# Power.net
KiCad netlist of a schematic drawn in Altium Designer
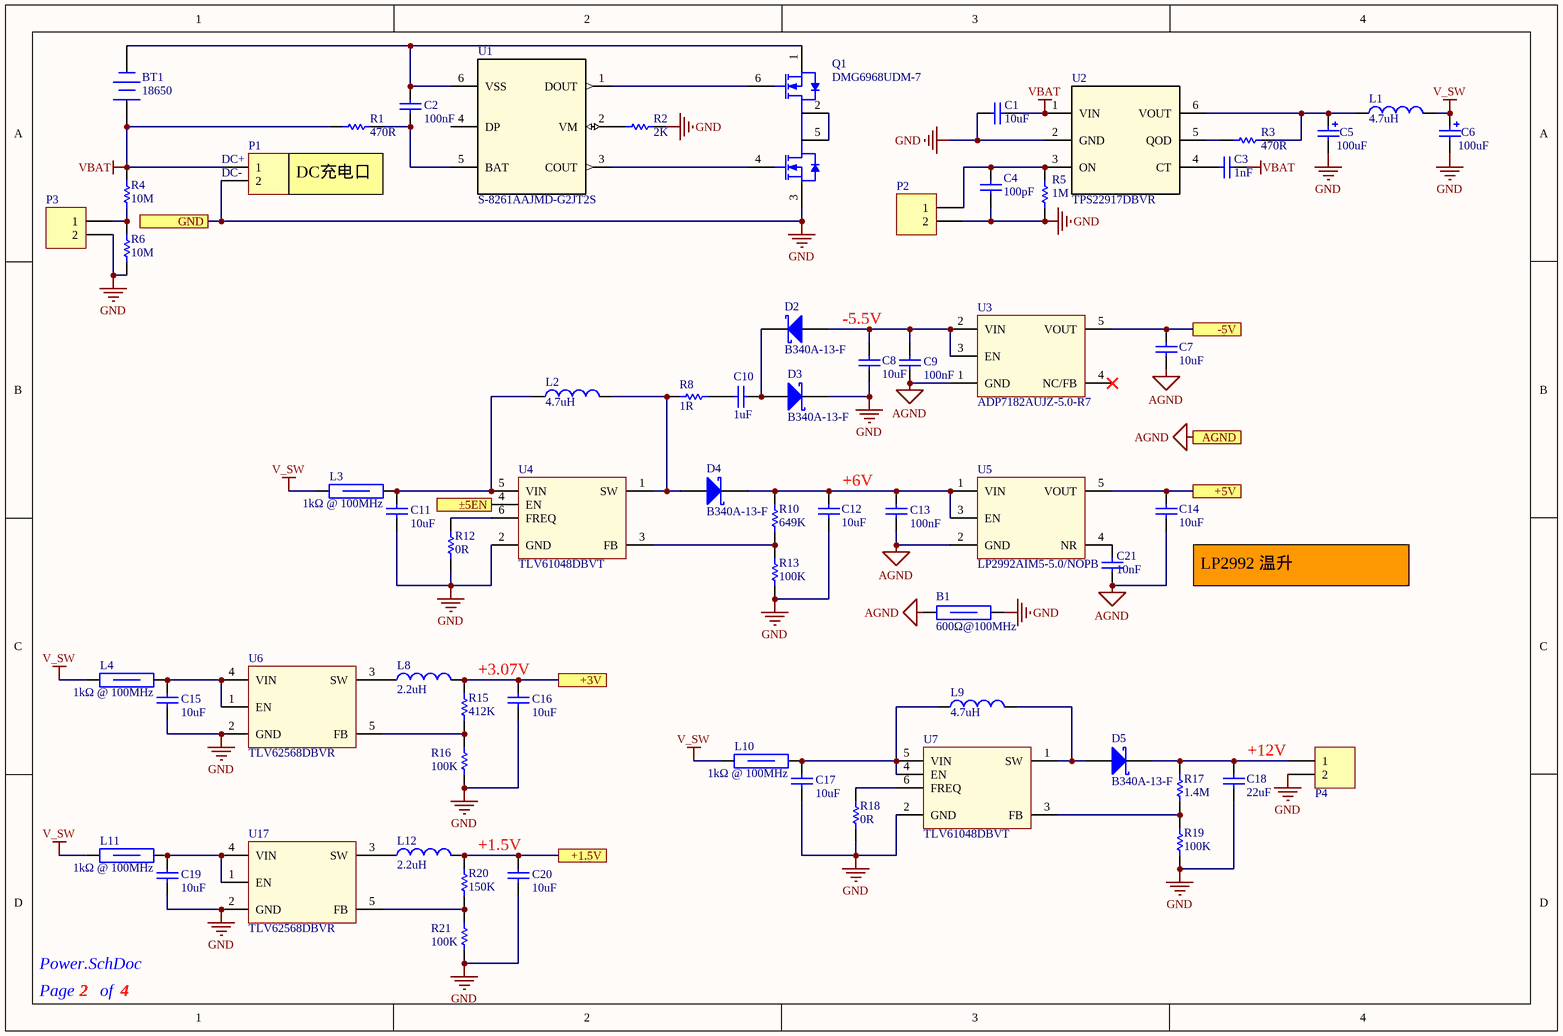
[diagram p0: Power.SchDoc]

(export (version "E")
  (design (tool "Eeschema 10.0.6"))
  (components
    (comp (ref "B1")
      (value "600Ω@100MHz")
      (footprint "R0805_L")
      (description "600Ω @ 100MHz \r\n线路数 1 \r\n额定电流（最大） 600mA \r\n直流电阻（DCR）（最大） 210mΩ")
      (libsource (lib "00Lib") (part "600Ω@100MHz"))
    )
    (comp (ref "BT1")
      (value "18650")
      (footprint "CP1X2")
      (description "18650单节直插电池仓")
      (libsource (lib "00Lib") (part "Battery_18650_DIP"))
    )
    (comp (ref "C1")
      (value "10uF")
      (footprint "R0805_C")
      (description "精度 ±10% \r\n容值 10uF \r\n额定电压 16V \r\n温漂系数（介质材料) X7R")
      (libsource (lib "00Lib") (part "10uF/0805/16V"))
    )
    (comp (ref "C2")
      (value "100nF")
      (footprint "R0603_C")
      (description "精度 ±10% \r\n容值 100nF \r\n额定电压 50V \r\n温漂系数（介质材料) X7R")
      (libsource (lib "00Lib") (part "100nF/0603/50V"))
    )
    (comp (ref "C3")
      (value "1nF")
      (footprint "R0603_C")
      (description "精度 ±5% \r\n容值 1nF \r\n额定电压 50V \r\n温漂系数（介质材料) C0G")
      (libsource (lib "00Lib") (part "1nF/0603/50V"))
    )
    (comp (ref "C4")
      (value "100pF")
      (footprint "R0603_C")
      (description "精度 ±5% \r\n容值 100pF \r\n额定电压 50V \r\n温漂系数（介质材料) C0G")
      (libsource (lib "00Lib") (part "100pF/0603/50V"))
    )
    (comp (ref "C5")
      (value "100uF")
      (footprint "CASE-E_7343")
      (description "钽电容 \r\n精度 ±10% \r\n容值 100uF \r\n额定电压 16V \r\nESR串联电阻 900 mΩ @ 100kHz \r\n工作温度 -55℃~125℃")
      (libsource (lib "00Lib") (part "Cap Pol/100uF/16V"))
    )
    (comp (ref "C6")
      (value "100uF")
      (footprint "CASE-E_7343")
      (description "钽电容 \r\n精度 ±10% \r\n容值 100uF \r\n额定电压 16V \r\nESR串联电阻 900 mΩ @ 100kHz \r\n工作温度 -55℃~125℃")
      (libsource (lib "00Lib") (part "Cap Pol/100uF/16V"))
    )
    (comp (ref "C7")
      (value "10uF")
      (footprint "R0805_C")
      (description "精度 ±10% \r\n容值 10uF \r\n额定电压 16V \r\n温漂系数（介质材料) X7R")
      (libsource (lib "00Lib") (part "10uF/0805/16V"))
    )
    (comp (ref "C8")
      (value "10uF")
      (footprint "R0805_C")
      (description "精度 ±10% \r\n容值 10uF \r\n额定电压 16V \r\n温漂系数（介质材料) X7R")
      (libsource (lib "00Lib") (part "10uF/0805/16V"))
    )
    (comp (ref "C9")
      (value "100nF")
      (footprint "R0603_C")
      (description "精度 ±10% \r\n容值 100nF \r\n额定电压 50V \r\n温漂系数（介质材料) X7R")
      (libsource (lib "00Lib") (part "100nF/0603/50V"))
    )
    (comp (ref "C10")
      (value "1uF")
      (footprint "R0603_C")
      (description "精度 ±10% \r\n容值 1uF \r\n额定电压 50V \r\n温漂系数（介质材料) X7R")
      (libsource (lib "00Lib") (part "1uF/0603/50V"))
    )
    (comp (ref "C11")
      (value "10uF")
      (footprint "R0805_C")
      (description "精度 ±10% \r\n容值 10uF \r\n额定电压 16V \r\n温漂系数（介质材料) X7R")
      (libsource (lib "00Lib") (part "10uF/0805/16V"))
    )
    (comp (ref "C12")
      (value "10uF")
      (footprint "R0805_C")
      (description "精度 ±10% \r\n容值 10uF \r\n额定电压 16V \r\n温漂系数（介质材料) X7R")
      (libsource (lib "00Lib") (part "10uF/0805/16V"))
    )
    (comp (ref "C13")
      (value "100nF")
      (footprint "R0603_C")
      (description "精度 ±10% \r\n容值 100nF \r\n额定电压 50V \r\n温漂系数（介质材料) X7R")
      (libsource (lib "00Lib") (part "100nF/0603/50V"))
    )
    (comp (ref "C14")
      (value "10uF")
      (footprint "R0805_C")
      (description "精度 ±10% \r\n容值 10uF \r\n额定电压 16V \r\n温漂系数（介质材料) X7R")
      (libsource (lib "00Lib") (part "10uF/0805/16V"))
    )
    (comp (ref "C15")
      (value "10uF")
      (footprint "R0805_C")
      (description "精度 ±10% \r\n容值 10uF \r\n额定电压 16V \r\n温漂系数（介质材料) X7R")
      (libsource (lib "00Lib") (part "10uF/0805/16V"))
    )
    (comp (ref "C16")
      (value "10uF")
      (footprint "R0805_C")
      (description "精度 ±10% \r\n容值 10uF \r\n额定电压 16V \r\n温漂系数（介质材料) X7R")
      (libsource (lib "00Lib") (part "10uF/0805/16V"))
    )
    (comp (ref "C17")
      (value "10uF")
      (footprint "R0805_C")
      (description "精度 ±10% \r\n容值 10uF \r\n额定电压 16V \r\n温漂系数（介质材料) X7R")
      (libsource (lib "00Lib") (part "10uF/0805/16V"))
    )
    (comp (ref "C18")
      (value "22uF")
      (footprint "R1210_C")
      (description "±10% \r\n容值 22uF \r\n额定电压 25V \r\n温漂系数（介质材料) X7R")
      (libsource (lib "00Lib") (part "22uF/1210/25V"))
    )
    (comp (ref "C19")
      (value "10uF")
      (footprint "R0805_C")
      (description "精度 ±10% \r\n容值 10uF \r\n额定电压 16V \r\n温漂系数（介质材料) X7R")
      (libsource (lib "00Lib") (part "10uF/0805/16V"))
    )
    (comp (ref "C20")
      (value "10uF")
      (footprint "R0805_C")
      (description "精度 ±10% \r\n容值 10uF \r\n额定电压 16V \r\n温漂系数（介质材料) X7R")
      (libsource (lib "00Lib") (part "10uF/0805/16V"))
    )
    (comp (ref "C21")
      (value "10nF")
      (footprint "R0603_C")
      (description "精度 ±5% \r\n容值 10nF \r\n额定电压 50V \r\n温漂系数（介质材料) C0G")
      (libsource (lib "00Lib") (part "10nF/0603/C0G/50V"))
    )
    (comp (ref "D2")
      (value "B340A-13-F")
      (footprint "SMA(DO-214AC)_S2")
      (description "直流反向耐压（Vr） 40V \r\n平均整流电流（Io） 3A \r\n正向压降（Vf） 550mV @ 3A")
      (libsource (lib "00Lib") (part "B340A-13-F"))
    )
    (comp (ref "D3")
      (value "B340A-13-F")
      (footprint "SMA(DO-214AC)_S2")
      (description "直流反向耐压（Vr） 40V \r\n平均整流电流（Io） 3A \r\n正向压降（Vf） 550mV @ 3A")
      (libsource (lib "00Lib") (part "B340A-13-F"))
    )
    (comp (ref "D4")
      (value "B340A-13-F")
      (footprint "SMA(DO-214AC)_S2")
      (description "直流反向耐压（Vr） 40V \r\n平均整流电流（Io） 3A \r\n正向压降（Vf） 550mV @ 3A")
      (libsource (lib "00Lib") (part "B340A-13-F"))
    )
    (comp (ref "D5")
      (value "B340A-13-F")
      (footprint "SMA(DO-214AC)_S2")
      (description "直流反向耐压（Vr） 40V \r\n平均整流电流（Io） 3A \r\n正向压降（Vf） 550mV @ 3A")
      (libsource (lib "00Lib") (part "B340A-13-F"))
    )
    (comp (ref "L1")
      (value "4.7uH")
      (footprint "NR2520")
      (description "精度 ±20% \r\n饱和电流 1.37A \r\n温升电流0.92A\r\n直流电阻（内阻） 377mΩ \r\n电感值 4.7uH")
      (libsource (lib "00Lib") (part "4.7uH/NR2520"))
    )
    (comp (ref "L2")
      (value "4.7uH")
      (footprint "NR2520")
      (description "精度 ±20% \r\n饱和电流 1.37A \r\n温升电流0.92A\r\n直流电阻（内阻） 377mΩ \r\n电感值 4.7uH")
      (libsource (lib "00Lib") (part "4.7uH/NR2520"))
    )
    (comp (ref "L3")
      (value "1kΩ @ 100MHz")
      (footprint "R1206_L")
      (description "阻抗 @ 频率 1kΩ @ 100MHz \r\n线路数 1 \r\n额定电流（最大） 2A \r\n直流电阻（DCR）（最大） 120mΩ")
      (libsource (lib "00Lib") (part "1kΩ@100MHz"))
    )
    (comp (ref "L4")
      (value "1kΩ @ 100MHz")
      (footprint "R1206_L")
      (description "阻抗 @ 频率 1kΩ @ 100MHz \r\n线路数 1 \r\n额定电流（最大） 2A \r\n直流电阻（DCR）（最大） 120mΩ")
      (libsource (lib "00Lib") (part "1kΩ@100MHz"))
    )
    (comp (ref "L8")
      (value "2.2uH")
      (footprint "NR2016")
      (description "精度 ±20% \r\n饱和电流 1.3A \r\n温升电流1.15A\r\n直流电阻（内阻） 175mΩ \r\n电感值 2.2uH")
      (libsource (lib "00Lib") (part "2.2uH/NR2016"))
    )
    (comp (ref "L9")
      (value "4.7uH")
      (footprint "NR2520")
      (description "精度 ±20% \r\n饱和电流 1.37A \r\n温升电流0.92A\r\n直流电阻（内阻） 377mΩ \r\n电感值 4.7uH")
      (libsource (lib "00Lib") (part "4.7uH/NR2520"))
    )
    (comp (ref "L10")
      (value "1kΩ @ 100MHz")
      (footprint "R1206_L")
      (description "阻抗 @ 频率 1kΩ @ 100MHz \r\n线路数 1 \r\n额定电流（最大） 2A \r\n直流电阻（DCR）（最大） 120mΩ")
      (libsource (lib "00Lib") (part "1kΩ@100MHz"))
    )
    (comp (ref "L11")
      (value "1kΩ @ 100MHz")
      (footprint "R1206_L")
      (description "阻抗 @ 频率 1kΩ @ 100MHz \r\n线路数 1 \r\n额定电流（最大） 2A \r\n直流电阻（DCR）（最大） 120mΩ")
      (libsource (lib "00Lib") (part "1kΩ@100MHz"))
    )
    (comp (ref "L12")
      (value "2.2uH")
      (footprint "NR2016")
      (description "精度 ±20% \r\n饱和电流 1.3A \r\n温升电流1.15A\r\n直流电阻（内阻） 175mΩ \r\n电感值 2.2uH")
      (libsource (lib "00Lib") (part "2.2uH/NR2016"))
    )
    (comp (ref "P1")
      (value "Header 2")
      (footprint "CP1X2")
      (description "Header, 2-Pin")
      (libsource (lib "") (part "Header 2_1"))
    )
    (comp (ref "P2")
      (value "Header 2")
      (footprint "CP1X2")
      (description "Header, 2-Pin")
      (libsource (lib "00Lib") (part "Header 2"))
    )
    (comp (ref "P3")
      (value "Header 2")
      (footprint "CP1X2")
      (description "Header, 2-Pin")
      (libsource (lib "00Lib") (part "Header 2"))
    )
    (comp (ref "P4")
      (value "Header 2")
      (footprint "CP1X2")
      (description "Header, 2-Pin")
      (libsource (lib "") (part "Header 2_1"))
    )
    (comp (ref "Q1")
      (value "DMG6968UDM-7")
      (footprint "DBV0006A_N")
      (libsource (lib "00Lib") (part "DMG6968UDM-7"))
    )
    (comp (ref "R1")
      (value "470R")
      (footprint "R0603_R")
      (description "精度 ±1% \r\n温度系数 ±100ppm/℃ \r\n功率 0.1W")
      (libsource (lib "00Lib") (part "470R/0603"))
    )
    (comp (ref "R2")
      (value "2K")
      (footprint "R0603_R")
      (description "精度 ±1% \r\n阻值 2kΩ \r\n温度系数 ±100ppm/℃ \r\n功率 0.1W")
      (libsource (lib "00Lib") (part "2K/0603"))
    )
    (comp (ref "R3")
      (value "470R")
      (footprint "R0603_R")
      (description "精度 ±1% \r\n温度系数 ±100ppm/℃ \r\n功率 0.1W")
      (libsource (lib "00Lib") (part "470R/0603"))
    )
    (comp (ref "R4")
      (value "10M")
      (footprint "R0603_R")
      (description "温度系数 ±250ppm/℃ \r\n精度 ±1% \r\n阻值 10MΩ \r\n功率 0.1W")
      (libsource (lib "00Lib") (part "10M/0603"))
    )
    (comp (ref "R5")
      (value "1M")
      (footprint "R0603_R")
      (description "阻值 1MΩ \r\n精度 ±1% \r\n温度系数 ±100ppm/℃ \r\n功率 0.1W")
      (libsource (lib "00Lib") (part "1M/0603"))
    )
    (comp (ref "R6")
      (value "10M")
      (footprint "R0603_R")
      (description "温度系数 ±250ppm/℃ \r\n精度 ±1% \r\n阻值 10MΩ \r\n功率 0.1W")
      (libsource (lib "00Lib") (part "10M/0603"))
    )
    (comp (ref "R8")
      (value "1R")
      (footprint "R0603_R")
      (description "±250ppm/℃ \r\n精度 ±1% \r\n阻值 1Ω \r\n功率 0.1W")
      (libsource (lib "00Lib") (part "1R/0603"))
    )
    (comp (ref "R10")
      (value "649K")
      (footprint "R0603_R")
      (description "649kΩ \r\n精度 ±1% \r\n温度系数 ±100ppm/℃ \r\n功率 0.1W")
      (libsource (lib "00Lib") (part "649K/0603"))
    )
    (comp (ref "R12")
      (value "0R")
      (footprint "R0603_R")
      (description "精度 ±1% \r\n阻值 0Ω \r\n功率 0.1W")
      (libsource (lib "00Lib") (part "0R/0603"))
    )
    (comp (ref "R13")
      (value "100K")
      (footprint "R0603_R")
      (description "精度 ±1% \r\n阻值 100kΩ \r\n温度系数 ±100ppm/℃ \r\n功率 0.1W")
      (libsource (lib "00Lib") (part "100K/0603"))
    )
    (comp (ref "R15")
      (value "412K")
      (footprint "R0603_R")
      (description "412kΩ \r\n精度 ±1% \r\n温度系数 ±100ppm/℃ \r\n功率 0.1W")
      (libsource (lib "00Lib") (part "412K/0603"))
    )
    (comp (ref "R16")
      (value "100K")
      (footprint "R0603_R")
      (description "精度 ±1% \r\n阻值 100kΩ \r\n温度系数 ±100ppm/℃ \r\n功率 0.1W")
      (libsource (lib "00Lib") (part "100K/0603"))
    )
    (comp (ref "R17")
      (value "1.4M")
      (footprint "R0603_R")
      (description "±250ppm/℃ \r\n精度 ±1% \r\n阻值 1.4MΩ \r\n功率 0.1W")
      (libsource (lib "00Lib") (part "1.4M/0603"))
    )
    (comp (ref "R18")
      (value "0R")
      (footprint "R0603_R")
      (description "精度 ±1% \r\n阻值 0Ω \r\n功率 0.1W")
      (libsource (lib "00Lib") (part "0R/0603"))
    )
    (comp (ref "R19")
      (value "100K")
      (footprint "R0603_R")
      (description "精度 ±1% \r\n阻值 100kΩ \r\n温度系数 ±100ppm/℃ \r\n功率 0.1W")
      (libsource (lib "00Lib") (part "100K/0603"))
    )
    (comp (ref "R20")
      (value "150K")
      (footprint "R0603_R")
      (description "150kΩ \r\n精度 ±1% \r\n温度系数 ±100ppm/℃ \r\n功率 0.1W")
      (libsource (lib "00Lib") (part "150K/0603"))
    )
    (comp (ref "R21")
      (value "100K")
      (footprint "R0603_R")
      (description "精度 ±1% \r\n阻值 100kΩ \r\n温度系数 ±100ppm/℃ \r\n功率 0.1W")
      (libsource (lib "00Lib") (part "100K/0603"))
    )
    (comp (ref "U1")
      (value "S-8261AAJMD-G2JT2S")
      (footprint "DBV0006A_N")
      (description "单节电池保护芯片\r\n过充4.325V\r\n过放2.5V\r\n过流150mV")
      (libsource (lib "00Lib") (part "S-8261AAJMD-G2JT2S"))
    )
    (comp (ref "U2")
      (value "TPS22917DBVR")
      (footprint "DBV0006A_N")
      (description "2A负载开关")
      (libsource (lib "00Lib") (part "TPS22917DBVR"))
    )
    (comp (ref "U3")
      (value "ADP7182AUJZ-5.0-R7")
      (footprint "SOT23-5")
      (description "–28 V、 −200 mA、低噪声线性稳压器")
      (libsource (lib "00Lib") (part "ADP7182AUJZ-5.0-R7"))
    )
    (comp (ref "U4")
      (value "TLV61048DBVT")
      (footprint "DBV0006A_N")
      (libsource (lib "00Lib") (part "TLV61048DBVT"))
    )
    (comp (ref "U5")
      (value "LP2992AIM5-5.0/NOPB")
      (footprint "SOT23-5")
      (libsource (lib "00Lib") (part "LP2992AIM5-5.0/NOPB"))
    )
    (comp (ref "U6")
      (value "TLV62568DBVR")
      (footprint "SOT23-5")
      (libsource (lib "00Lib") (part "TLV62568DBVR"))
    )
    (comp (ref "U7")
      (value "TLV61048DBVT")
      (footprint "DBV0006A_N")
      (libsource (lib "00Lib") (part "TLV61048DBVT"))
    )
    (comp (ref "U17")
      (value "TLV62568DBVR")
      (footprint "SOT23-5")
      (libsource (lib "00Lib") (part "TLV62568DBVR"))
    )
  )
  (nets
    (net (code "1") (name "/+1.5V") (class "Default")
      (node (ref "C20") (pin "2") (pinfunction "2_2") (pintype "passive"))
      (node (ref "L12") (pin "2") (pinfunction "2_2") (pintype "passive"))
      (node (ref "R20") (pin "2") (pinfunction "2_2") (pintype "passive"))
    )
    (net (code "2") (name "/+3V") (class "Default")
      (node (ref "C16") (pin "2") (pinfunction "2_2") (pintype "passive"))
      (node (ref "L8") (pin "2") (pinfunction "2_2") (pintype "passive"))
      (node (ref "R15") (pin "2") (pinfunction "2_2") (pintype "passive"))
    )
    (net (code "3") (name "/+5V") (class "Default")
      (node (ref "C14") (pin "1") (pinfunction "1_1") (pintype "passive"))
      (node (ref "U5") (pin "5") (pinfunction "VOUT_5") (pintype "power_in"))
    )
    (net (code "4") (name "/-5V") (class "Default")
      (node (ref "C7") (pin "1") (pinfunction "1_1") (pintype "passive"))
      (node (ref "U3") (pin "5") (pinfunction "VOUT_5") (pintype "power_in"))
    )
    (net (code "5") (name "/±5EN") (class "Default")
      (node (ref "U4") (pin "4") (pinfunction "EN_4") (pintype "passive"))
    )
    (net (code "6") (name "AGND") (class "Default")
      (node (ref "B1") (pin "1") (pinfunction "1_1") (pintype "passive"))
      (node (ref "C13") (pin "2") (pinfunction "2_2") (pintype "passive"))
      (node (ref "C14") (pin "2") (pinfunction "2_2") (pintype "passive"))
      (node (ref "C21") (pin "1") (pinfunction "1_1") (pintype "passive"))
      (node (ref "C7") (pin "2") (pinfunction "2_2") (pintype "passive"))
      (node (ref "C9") (pin "2") (pinfunction "2_2") (pintype "passive"))
      (node (ref "U3") (pin "1") (pinfunction "GND_1") (pintype "power_in"))
      (node (ref "U5") (pin "2") (pinfunction "GND_2") (pintype "power_in"))
    )
    (net (code "7") (name "GND") (class "Default")
      (node (ref "B1") (pin "2") (pinfunction "2_2") (pintype "passive"))
      (node (ref "C1") (pin "1") (pinfunction "1_1") (pintype "passive"))
      (node (ref "C11") (pin "1") (pinfunction "1_1") (pintype "passive"))
      (node (ref "C12") (pin "1") (pinfunction "1_1") (pintype "passive"))
      (node (ref "C15") (pin "1") (pinfunction "1_1") (pintype "passive"))
      (node (ref "C16") (pin "1") (pinfunction "1_1") (pintype "passive"))
      (node (ref "C17") (pin "1") (pinfunction "1_1") (pintype "passive"))
      (node (ref "C18") (pin "1") (pinfunction "1_1") (pintype "passive"))
      (node (ref "C19") (pin "1") (pinfunction "1_1") (pintype "passive"))
      (node (ref "C20") (pin "1") (pinfunction "1_1") (pintype "passive"))
      (node (ref "C4") (pin "1") (pinfunction "1_1") (pintype "passive"))
      (node (ref "C5") (pin "2") (pinfunction "2_2") (pintype "passive"))
      (node (ref "C6") (pin "2") (pinfunction "2_2") (pintype "passive"))
      (node (ref "C8") (pin "2") (pinfunction "2_2") (pintype "passive"))
      (node (ref "D3") (pin "2") (pinfunction "K_2") (pintype "passive"))
      (node (ref "P1") (pin "2") (pinfunction "2_2") (pintype "passive"))
      (node (ref "P2") (pin "2") (pinfunction "2_2") (pintype "passive"))
      (node (ref "P3") (pin "2") (pinfunction "2_2") (pintype "passive"))
      (node (ref "P4") (pin "2") (pinfunction "2_2") (pintype "passive"))
      (node (ref "Q1") (pin "3") (pinfunction "S2_3") (pintype "passive"))
      (node (ref "R12") (pin "1") (pinfunction "1_1") (pintype "passive"))
      (node (ref "R13") (pin "1") (pinfunction "1_1") (pintype "passive"))
      (node (ref "R16") (pin "1") (pinfunction "1_1") (pintype "passive"))
      (node (ref "R18") (pin "1") (pinfunction "1_1") (pintype "passive"))
      (node (ref "R19") (pin "1") (pinfunction "1_1") (pintype "passive"))
      (node (ref "R2") (pin "2") (pinfunction "2_2") (pintype "passive"))
      (node (ref "R21") (pin "1") (pinfunction "1_1") (pintype "passive"))
      (node (ref "R5") (pin "1") (pinfunction "1_1") (pintype "passive"))
      (node (ref "R6") (pin "2") (pinfunction "2_2") (pintype "passive"))
      (node (ref "U17") (pin "2") (pinfunction "GND_2") (pintype "power_in"))
      (node (ref "U2") (pin "2") (pinfunction "GND_2") (pintype "passive"))
      (node (ref "U4") (pin "2") (pinfunction "GND_2") (pintype "power_in"))
      (node (ref "U6") (pin "2") (pinfunction "GND_2") (pintype "power_in"))
      (node (ref "U7") (pin "2") (pinfunction "GND_2") (pintype "power_in"))
    )
    (net (code "8") (name "Net-(BT1--)") (class "Default")
      (node (ref "BT1") (pin "2") (pinfunction "-_2") (pintype "passive"))
      (node (ref "C2") (pin "1") (pinfunction "1_1") (pintype "passive"))
      (node (ref "Q1") (pin "1") (pinfunction "S1_1") (pintype "passive"))
      (node (ref "U1") (pin "6") (pinfunction "VSS_6") (pintype "passive"))
    )
    (net (code "9") (name "Net-(C10-Pad2)") (class "Default")
      (node (ref "C10") (pin "2") (pinfunction "2_2") (pintype "passive"))
      (node (ref "R8") (pin "2") (pinfunction "2_2") (pintype "passive"))
    )
    (net (code "10") (name "Net-(D2-A)") (class "Default")
      (node (ref "C8") (pin "1") (pinfunction "1_1") (pintype "passive"))
      (node (ref "C9") (pin "1") (pinfunction "1_1") (pintype "passive"))
      (node (ref "D2") (pin "1") (pinfunction "A_1") (pintype "passive"))
      (node (ref "U3") (pin "2") (pinfunction "VIN_2") (pintype "power_in"))
      (node (ref "U3") (pin "3") (pinfunction "EN_3") (pintype "passive"))
    )
    (net (code "11") (name "Net-(D2-K)") (class "Default")
      (node (ref "C10") (pin "1") (pinfunction "1_1") (pintype "passive"))
      (node (ref "D2") (pin "2") (pinfunction "K_2") (pintype "passive"))
      (node (ref "D3") (pin "1") (pinfunction "A_1") (pintype "passive"))
    )
    (net (code "12") (name "Net-(D4-A)") (class "Default")
      (node (ref "D4") (pin "1") (pinfunction "A_1") (pintype "passive"))
      (node (ref "L2") (pin "2") (pinfunction "2_2") (pintype "passive"))
      (node (ref "R8") (pin "1") (pinfunction "1_1") (pintype "passive"))
      (node (ref "U4") (pin "1") (pinfunction "SW_1") (pintype "power_in"))
    )
    (net (code "13") (name "Net-(D4-K)") (class "Default")
      (node (ref "C12") (pin "2") (pinfunction "2_2") (pintype "passive"))
      (node (ref "C13") (pin "1") (pinfunction "1_1") (pintype "passive"))
      (node (ref "D4") (pin "2") (pinfunction "K_2") (pintype "passive"))
      (node (ref "R10") (pin "2") (pinfunction "2_2") (pintype "passive"))
      (node (ref "U5") (pin "1") (pinfunction "VIN_1") (pintype "power_in"))
      (node (ref "U5") (pin "3") (pinfunction "EN_3") (pintype "passive"))
    )
    (net (code "14") (name "Net-(D5-A)") (class "Default")
      (node (ref "D5") (pin "1") (pinfunction "A_1") (pintype "passive"))
      (node (ref "L9") (pin "2") (pinfunction "2_2") (pintype "passive"))
      (node (ref "U7") (pin "1") (pinfunction "SW_1") (pintype "power_in"))
    )
    (net (code "15") (name "Net-(D5-K)") (class "Default")
      (node (ref "C18") (pin "2") (pinfunction "2_2") (pintype "passive"))
      (node (ref "D5") (pin "2") (pinfunction "K_2") (pintype "passive"))
      (node (ref "P4") (pin "1") (pinfunction "1_1") (pintype "passive"))
      (node (ref "R17") (pin "2") (pinfunction "2_2") (pintype "passive"))
    )
    (net (code "16") (name "Net-(P3-Pad1)") (class "Default")
      (node (ref "P3") (pin "1") (pinfunction "1_1") (pintype "passive"))
      (node (ref "R4") (pin "2") (pinfunction "2_2") (pintype "passive"))
      (node (ref "R6") (pin "1") (pinfunction "1_1") (pintype "passive"))
    )
    (net (code "17") (name "Net-(Q1-D1{slash}D2-Pad2)") (class "Default")
      (node (ref "Q1") (pin "2") (pinfunction "D1/D2_2") (pintype "passive"))
      (node (ref "Q1") (pin "5") (pinfunction "D1/D2_5") (pintype "passive"))
    )
    (net (code "18") (name "Net-(Q1-G1)") (class "Default")
      (node (ref "Q1") (pin "6") (pinfunction "G1_6") (pintype "passive"))
      (node (ref "U1") (pin "1") (pinfunction "DOUT_1") (pintype "output"))
    )
    (net (code "19") (name "Net-(Q1-G2)") (class "Default")
      (node (ref "Q1") (pin "4") (pinfunction "G2_4") (pintype "passive"))
      (node (ref "U1") (pin "3") (pinfunction "COUT_3") (pintype "output"))
    )
    (net (code "20") (name "Net-(U1-BAT)") (class "Default")
      (node (ref "C2") (pin "2") (pinfunction "2_2") (pintype "passive"))
      (node (ref "R1") (pin "2") (pinfunction "2_2") (pintype "passive"))
      (node (ref "U1") (pin "5") (pinfunction "BAT_5") (pintype "power_in"))
    )
    (net (code "21") (name "Net-(U1-VM)") (class "Default")
      (node (ref "R2") (pin "1") (pinfunction "1_1") (pintype "passive"))
      (node (ref "U1") (pin "2") (pinfunction "VM_2") (pintype "bidirectional"))
    )
    (net (code "22") (name "Net-(U2-CT)") (class "Default")
      (node (ref "C3") (pin "1") (pinfunction "1_1") (pintype "passive"))
      (node (ref "U2") (pin "4") (pinfunction "CT_4") (pintype "power_in"))
    )
    (net (code "23") (name "Net-(U2-ON)") (class "Default")
      (node (ref "C4") (pin "2") (pinfunction "2_2") (pintype "passive"))
      (node (ref "P2") (pin "1") (pinfunction "1_1") (pintype "passive"))
      (node (ref "R5") (pin "2") (pinfunction "2_2") (pintype "passive"))
      (node (ref "U2") (pin "3") (pinfunction "ON_3") (pintype "passive"))
    )
    (net (code "24") (name "Net-(U2-QOD)") (class "Default")
      (node (ref "R3") (pin "1") (pinfunction "1_1") (pintype "passive"))
      (node (ref "U2") (pin "5") (pinfunction "QOD_5") (pintype "passive"))
    )
    (net (code "25") (name "Net-(U2-VOUT)") (class "Default")
      (node (ref "C5") (pin "1") (pinfunction "1_1") (pintype "passive"))
      (node (ref "L1") (pin "1") (pinfunction "1_1") (pintype "passive"))
      (node (ref "R3") (pin "2") (pinfunction "2_2") (pintype "passive"))
      (node (ref "U2") (pin "6") (pinfunction "VOUT_6") (pintype "power_in"))
    )
    (net (code "26") (name "Net-(U4-FB)") (class "Default")
      (node (ref "R10") (pin "1") (pinfunction "1_1") (pintype "passive"))
      (node (ref "R13") (pin "2") (pinfunction "2_2") (pintype "passive"))
      (node (ref "U4") (pin "3") (pinfunction "FB_3") (pintype "power_in"))
    )
    (net (code "27") (name "Net-(U4-FREQ)") (class "Default")
      (node (ref "R12") (pin "2") (pinfunction "2_2") (pintype "passive"))
      (node (ref "U4") (pin "6") (pinfunction "FREQ_6") (pintype "passive"))
    )
    (net (code "28") (name "Net-(U4-VIN)") (class "Default")
      (node (ref "C11") (pin "2") (pinfunction "2_2") (pintype "passive"))
      (node (ref "L2") (pin "1") (pinfunction "1_1") (pintype "passive"))
      (node (ref "L3") (pin "2") (pinfunction "2_2") (pintype "passive"))
      (node (ref "U4") (pin "5") (pinfunction "VIN_5") (pintype "passive"))
    )
    (net (code "29") (name "Net-(U5-NR)") (class "Default")
      (node (ref "C21") (pin "2") (pinfunction "2_2") (pintype "passive"))
      (node (ref "U5") (pin "4") (pinfunction "NR_4") (pintype "passive"))
    )
    (net (code "30") (name "Net-(U6-EN)") (class "Default")
      (node (ref "C15") (pin "2") (pinfunction "2_2") (pintype "passive"))
      (node (ref "L4") (pin "2") (pinfunction "2_2") (pintype "passive"))
      (node (ref "U6") (pin "1") (pinfunction "EN_1") (pintype "power_in"))
      (node (ref "U6") (pin "4") (pinfunction "VIN_4") (pintype "passive"))
    )
    (net (code "31") (name "Net-(U6-FB)") (class "Default")
      (node (ref "R15") (pin "1") (pinfunction "1_1") (pintype "passive"))
      (node (ref "R16") (pin "2") (pinfunction "2_2") (pintype "passive"))
      (node (ref "U6") (pin "5") (pinfunction "FB_5") (pintype "power_in"))
    )
    (net (code "32") (name "Net-(U6-SW)") (class "Default")
      (node (ref "L8") (pin "1") (pinfunction "1_1") (pintype "passive"))
      (node (ref "U6") (pin "3") (pinfunction "SW_3") (pintype "passive"))
    )
    (net (code "33") (name "Net-(U7-EN)") (class "Default")
      (node (ref "C17") (pin "2") (pinfunction "2_2") (pintype "passive"))
      (node (ref "L10") (pin "2") (pinfunction "2_2") (pintype "passive"))
      (node (ref "L9") (pin "1") (pinfunction "1_1") (pintype "passive"))
      (node (ref "U7") (pin "4") (pinfunction "EN_4") (pintype "passive"))
      (node (ref "U7") (pin "5") (pinfunction "VIN_5") (pintype "passive"))
    )
    (net (code "34") (name "Net-(U7-FB)") (class "Default")
      (node (ref "R17") (pin "1") (pinfunction "1_1") (pintype "passive"))
      (node (ref "R19") (pin "2") (pinfunction "2_2") (pintype "passive"))
      (node (ref "U7") (pin "3") (pinfunction "FB_3") (pintype "power_in"))
    )
    (net (code "35") (name "Net-(U7-FREQ)") (class "Default")
      (node (ref "R18") (pin "2") (pinfunction "2_2") (pintype "passive"))
      (node (ref "U7") (pin "6") (pinfunction "FREQ_6") (pintype "passive"))
    )
    (net (code "36") (name "Net-(U17-EN)") (class "Default")
      (node (ref "C19") (pin "2") (pinfunction "2_2") (pintype "passive"))
      (node (ref "L11") (pin "2") (pinfunction "2_2") (pintype "passive"))
      (node (ref "U17") (pin "1") (pinfunction "EN_1") (pintype "power_in"))
      (node (ref "U17") (pin "4") (pinfunction "VIN_4") (pintype "passive"))
    )
    (net (code "37") (name "Net-(U17-FB)") (class "Default")
      (node (ref "R20") (pin "1") (pinfunction "1_1") (pintype "passive"))
      (node (ref "R21") (pin "2") (pinfunction "2_2") (pintype "passive"))
      (node (ref "U17") (pin "5") (pinfunction "FB_5") (pintype "power_in"))
    )
    (net (code "38") (name "Net-(U17-SW)") (class "Default")
      (node (ref "L12") (pin "1") (pinfunction "1_1") (pintype "passive"))
      (node (ref "U17") (pin "3") (pinfunction "SW_3") (pintype "passive"))
    )
    (net (code "39") (name "VBAT") (class "Default")
      (node (ref "BT1") (pin "1") (pinfunction "+_1") (pintype "passive"))
      (node (ref "C1") (pin "2") (pinfunction "2_2") (pintype "passive"))
      (node (ref "C3") (pin "2") (pinfunction "2_2") (pintype "passive"))
      (node (ref "P1") (pin "1") (pinfunction "1_1") (pintype "passive"))
      (node (ref "R1") (pin "1") (pinfunction "1_1") (pintype "passive"))
      (node (ref "R4") (pin "1") (pinfunction "1_1") (pintype "passive"))
      (node (ref "U2") (pin "1") (pinfunction "VIN_1") (pintype "power_in"))
    )
    (net (code "40") (name "V_SW") (class "Default")
      (node (ref "C6") (pin "1") (pinfunction "1_1") (pintype "passive"))
      (node (ref "L1") (pin "2") (pinfunction "2_2") (pintype "passive"))
      (node (ref "L10") (pin "1") (pinfunction "1_1") (pintype "passive"))
      (node (ref "L11") (pin "1") (pinfunction "1_1") (pintype "passive"))
      (node (ref "L3") (pin "1") (pinfunction "1_1") (pintype "passive"))
      (node (ref "L4") (pin "1") (pinfunction "1_1") (pintype "passive"))
    )
    (net (code "41") (name "unconnected-(U1-DP-Pad4)") (class "Default")
      (node (ref "U1") (pin "4") (pinfunction "DP_4") (pintype "power_in"))
    )
    (net (code "42") (name "unconnected-(U3-NC{slash}FB-Pad4)") (class "Default")
      (node (ref "U3") (pin "4") (pinfunction "NC/FB_4") (pintype "passive+no_connect"))
    )
  )
)
